# RP5_Left_Board.net
KiCad netlist of a schematic drawn in Altium Designer
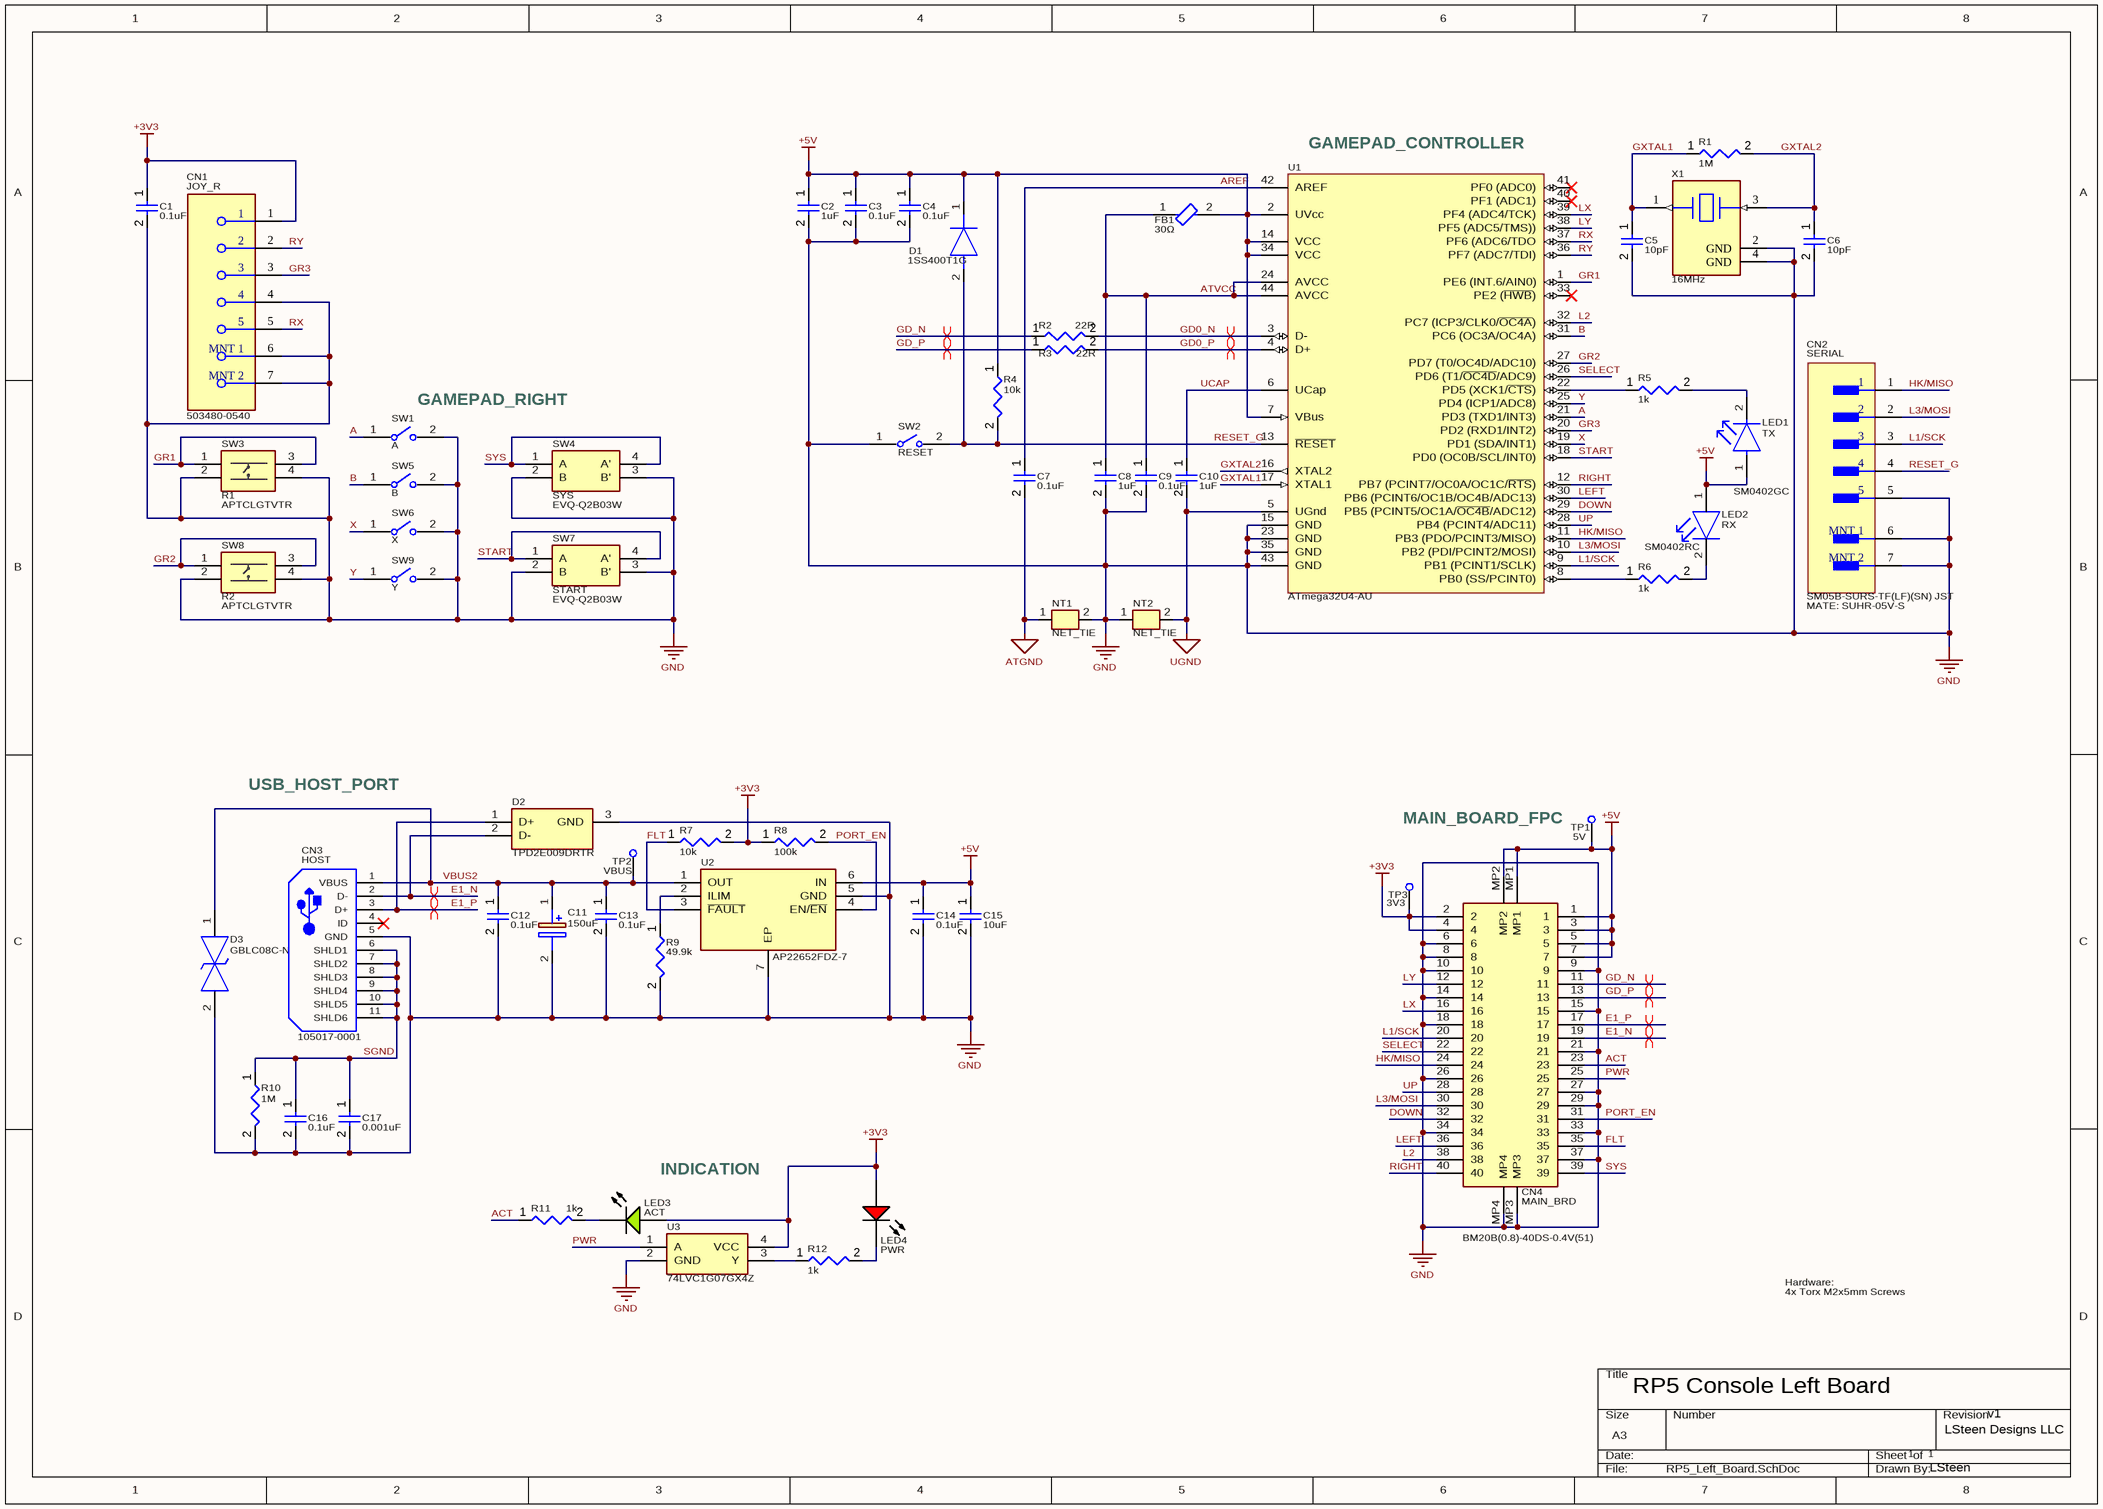
[diagram p0: RP5_Left_Board.SchDoc]

(export (version "E")
  (design (tool "Eeschema 10.0.6"))
  (components
    (comp (ref "C1")
      (value "0.1uF")
      (footprint "CAPC1005X56X25LL10T15")
      (description "Chip Capacitor, 0.1 uF, +/- 5%, 16 V, 0402 (1005 Metric)")
      (fields (field (name "TOLERANCE") "5%"))
      (libsource (lib "Colorado Technical University") (part "CAP-NP-2"))
    )
    (comp (ref "C2")
      (value "1uF")
      (footprint "CAPC0603(1608)100_L")
      (description "Chip Capacitor, 1uF +/-20%, 10V, 0603, Thickness 1 mm")
      (fields (field (name "TOLERANCE") "10%"))
      (libsource (lib "Colorado Technical University") (part "CAP-NP-2"))
    )
    (comp (ref "C3")
      (value "0.1uF")
      (footprint "CAPC1005X56X25LL10T15")
      (description "Chip Capacitor, 0.1 uF, +/- 5%, 16 V, 0402 (1005 Metric)")
      (fields (field (name "TOLERANCE") "5%"))
      (libsource (lib "Colorado Technical University") (part "CAP-NP-2"))
    )
    (comp (ref "C4")
      (value "0.1uF")
      (footprint "CAPC1005X56X25LL10T15")
      (description "Chip Capacitor, 0.1 uF, +/- 5%, 16 V, 0402 (1005 Metric)")
      (fields (field (name "TOLERANCE") "5%"))
      (libsource (lib "Colorado Technical University") (part "CAP-NP-2"))
    )
    (comp (ref "C5")
      (value "10pF")
      (footprint "CAPC1005X56X25LL10T15")
      (description "Chip Capacitor, 10 pF, +/- 5%, 16 V, 0402 (1005 Metric)")
      (fields (field (name "TOLERANCE") "5%"))
      (libsource (lib "Colorado Technical University") (part "CAP-NP-2"))
    )
    (comp (ref "C6")
      (value "10pF")
      (footprint "CAPC1005X56X25LL10T15")
      (description "Chip Capacitor, 10 pF, +/- 5%, 16 V, 0402 (1005 Metric)")
      (fields (field (name "TOLERANCE") "5%"))
      (libsource (lib "Colorado Technical University") (part "CAP-NP-2"))
    )
    (comp (ref "C7")
      (value "0.1uF")
      (footprint "CAPC1005X56X25LL10T15")
      (description "Chip Capacitor, 0.1 uF, +/- 5%, 16 V, 0402 (1005 Metric)")
      (fields (field (name "TOLERANCE") "5%"))
      (libsource (lib "Colorado Technical University") (part "CAP-NP-2"))
    )
    (comp (ref "C8")
      (value "1uF")
      (footprint "CAPC0603(1608)100_L")
      (description "Chip Capacitor, 1uF +/-20%, 10V, 0603, Thickness 1 mm")
      (fields (field (name "TOLERANCE") "10%"))
      (libsource (lib "Colorado Technical University") (part "CAP-NP-2"))
    )
    (comp (ref "C9")
      (value "0.1uF")
      (footprint "CAPC1005X56X25LL10T15")
      (description "Chip Capacitor, 0.1 uF, +/- 5%, 16 V, 0402 (1005 Metric)")
      (fields (field (name "TOLERANCE") "5%"))
      (libsource (lib "Colorado Technical University") (part "CAP-NP-2"))
    )
    (comp (ref "C10")
      (value "1uF")
      (footprint "CAPC0603(1608)100_L")
      (description "Chip Capacitor, 1uF +/-20%, 10V, 0603, Thickness 1 mm")
      (fields (field (name "TOLERANCE") "10%"))
      (libsource (lib "Colorado Technical University") (part "CAP-NP-2"))
    )
    (comp (ref "C11")
      (value "150uF")
      (footprint "SamacSys:CAPPM7344X310N")
      (description "Capacitor Polarised")
      (fields
        (field (name "MANUFACTURER_PART_NUMBER") "TPSD157K016S0125")
        (field (name "MOUSER PART NUMBER") "581-TPSD157K016S0125")
      )
      (libsource (lib "SamacSys") (part "TPSD157K016S0125"))
    )
    (comp (ref "C12")
      (value "0.1uF")
      (footprint "CAPC1005X56X25LL10T15")
      (description "Chip Capacitor, 0.1 uF, +/- 5%, 16 V, 0402 (1005 Metric)")
      (fields (field (name "TOLERANCE") "5%"))
      (libsource (lib "Colorado Technical University") (part "CAP-NP-2"))
    )
    (comp (ref "C13")
      (value "0.1uF")
      (footprint "CAPC1005X56X25LL10T15")
      (description "Chip Capacitor, 0.1 uF, +/- 5%, 16 V, 0402 (1005 Metric)")
      (fields (field (name "TOLERANCE") "5%"))
      (libsource (lib "Colorado Technical University") (part "CAP-NP-2"))
    )
    (comp (ref "C14")
      (value "0.1uF")
      (footprint "CAPC1005X56X25LL10T15")
      (description "Chip Capacitor, 0.1 uF, +/- 5%, 16 V, 0402 (1005 Metric)")
      (fields (field (name "TOLERANCE") "5%"))
      (libsource (lib "Colorado Technical University") (part "CAP-NP-2"))
    )
    (comp (ref "C15")
      (value "10uF")
      (footprint "CAPC0805(2012)145_L")
      (description "Chip Capacitor, 10µF +/-20%, 25V, 0805, Thickness 1.45 mm")
      (fields (field (name "TOLERANCE") "10%"))
      (libsource (lib "Colorado Technical University") (part "CAP-NP-2"))
    )
    (comp (ref "C16")
      (value "0.1uF")
      (footprint "CAPC1005X56X25LL10T15")
      (description "Chip Capacitor, 0.1 uF, +/- 5%, 16 V, 0402 (1005 Metric)")
      (fields (field (name "TOLERANCE") "5%"))
      (libsource (lib "Colorado Technical University") (part "CAP-NP-2"))
    )
    (comp (ref "C17")
      (value "0.001uF")
      (footprint "CAPC1005X56X25LL10T15")
      (description "Chip Capacitor, 0.1 uF, +/- 5%, 16 V, 0402 (1005 Metric)")
      (fields (field (name "TOLERANCE") "5%"))
      (libsource (lib "Colorado Technical University") (part "CAP-NP-2"))
    )
    (comp (ref "CN1")
      (value "JOY_R")
      (footprint "FP-503480-0540-MFG")
      (description "503480-0540 Connector FFC/FPC SKT 5 Position 0.5mm Solder Right Angle Surface Mount T/R")
      (libsource (lib "Altium Content Vault") (part "6b037d2877ced340e1c65ac82253790"))
    )
    (comp (ref "CN2")
      (value "SERIAL")
      (footprint "FP-SM05B-SURS-TF_LF_SN-MFG")
      (description "CONN HEADER SMD R/A 5POS 0.8MM")
      (libsource (lib "Altium Content Vault") (part "SM05B-SURS-TF_LF_SN"))
    )
    (comp (ref "CN3")
      (value "HOST")
      (footprint "105017-0001")
      (description "Micro USB Connector")
      (fields
        (field (name "MANUFACTURER_PART_NUMBER") "105017-0001")
        (field (name "MOUSER PART NUMBER") "538-105017-0001")
      )
      (libsource (lib "SamacSys") (part "105017-0001"))
    )
    (comp (ref "CN4")
      (value "MAIN_BRD")
      (footprint "SamacSys:BM20B0840DS04V51")
      (description "Connector")
      (fields
        (field (name "MANUFACTURER_PART_NUMBER") "BM20B(0.8)-40DS-0.4V(51)")
        (field (name "MOUSER PART NUMBER") "798-BM20B0840DS04V51")
      )
      (libsource (lib "SamacSys") (part "BM20B(0.8)-40DS-0.4V(51)"))
    )
    (comp (ref "D1")
      (value "1SS400T1G")
      (footprint "SamacSys:SODFL1608X70N")
      (description "Diode")
      (fields (field (name "MOUSER PART NUMBER") "863-1SS400T1G"))
      (libsource (lib "SamacSys") (part "1SS400T1G"))
    )
    (comp (ref "D2")
      (value "TPD2E009DRTR")
      (footprint "SamacSys:SOTFL35P100X50-3N")
      (description "Integrated Circuit")
      (fields (field (name "MOUSER PART NUMBER") "595-TPD2E009DRTR"))
      (libsource (lib "SamacSys") (part "TPD2E009DRTR"))
    )
    (comp (ref "D3")
      (value "GBLC08C-N")
      (footprint "SOD-323_L1.8-W1.3-LS2.5-BI")
      (description "ESD DIODE-BI_LCSC#C314256")
      (libsource (lib "Schlib1") (part "GBLC08C-N"))
    )
    (comp (ref "FB1")
      (value "30Ω")
      (footprint "FP-MH2029-MFG")
      (description "FERRITE BEAD 30 OHM 0805 1LN")
      (fields
        (field (name "MANUFACTURER PART NUMBER") "MH2029-300Y")
        (field (name "OCTOPART") "https://octopart.com/mh2029-300y-bourns-756929")
      )
      (libsource (lib "Altium Content Vault") (part "5f30dd21d616792df468990f7003faa"))
    )
    (comp (ref "LED1")
      (value "TX")
      (footprint "FP-SM0402GC-MFG")
      (description "LED GREEN CLEAR 0402 SMD SUPPLIMENT LCSC MHT136CGCT")
      (libsource (lib "Altium Content Vault") (part "ab1c01a81903e929fc6c44469aada92"))
    )
    (comp (ref "LED2")
      (value "RX")
      (footprint "FP-SM0402RC-MFG")
      (description "LED RED CLEAR 0402 SMD SUPPLIMENT LCSC MHT136CRCT")
      (libsource (lib "") (part "ab1c01a81903e929fc6c44469aada92_1"))
    )
    (comp (ref "LED3")
      (value "ACT")
      (footprint "LED_0603")
      (fields (field (name "MPN") "BZ-C0603-K4-E1"))
      (libsource (lib "SamacSys") (part "BZ-C0603-K4-E1"))
    )
    (comp (ref "LED4")
      (value "PWR")
      (footprint "EVRL-0603-2_V")
      (description "Chip LED, Red, 5 V, 25 mA, -40 to 85 degC, 2-Pin SMD (0603), RoHS, Tape and Reel")
      (fields
        (field (name "MANUFACTURER") "Everlight Electronics")
        (field (name "MANUFACTURER PART NUMBER") "19-217/R6C-AL1M2VY/3T")
      )
      (libsource (lib "Altium Content Vault") (part "LED-RED-AK-2"))
    )
    (comp (ref "NT1") (value "NET_TIE") (footprint "NET_TIE1") (libsource (lib "Schlib1") (part "NET_TIE")))
    (comp (ref "NT2") (value "NET_TIE") (footprint "NET_TIE1") (libsource (lib "Schlib1") (part "NET_TIE")))
    (comp (ref "R1")
      (value "1M")
      (footprint "RESC0402(1005)_L")
      (description "Chip Resistor, 1 MOhms, +/-5 %, 63 mW, -55 to 155 degC, 0402")
      (fields (field (name "TOLERANCE") "5%") (field (name "POWER") "63mW"))
      (libsource (lib "Colorado Technical University") (part "RES-2"))
    )
    (comp (ref "R2")
      (value "22R")
      (footprint "RESC0402(1005)_L")
      (description "Chip Resistor, 22 Ohms, +/-5 %, 63 mW, -55 to 155 degC, 0402")
      (fields (field (name "TOLERANCE") "5%") (field (name "POWER") "63mW"))
      (libsource (lib "Colorado Technical University") (part "RES-2"))
    )
    (comp (ref "R3")
      (value "22R")
      (footprint "RESC0402(1005)_L")
      (description "Chip Resistor, 22 Ohms, +/-5 %, 63 mW, -55 to 155 degC, 0402")
      (fields (field (name "TOLERANCE") "5%") (field (name "POWER") "63mW"))
      (libsource (lib "Colorado Technical University") (part "RES-2"))
    )
    (comp (ref "R4")
      (value "10k")
      (footprint "RESC0402(1005)_L")
      (description "Chip Resistor, 10 kOhms, +/-5 %, 63 mW, -55 to 155 degC, 0402")
      (fields (field (name "TOLERANCE") "5%") (field (name "POWER") "63mW"))
      (libsource (lib "Colorado Technical University") (part "RES-2"))
    )
    (comp (ref "R5")
      (value "1k")
      (footprint "RESC0402(1005)_L")
      (description "Chip Resistor, 1 kOhms, +/-5 %, 63 mW, -55 to 155 degC, 0402")
      (fields (field (name "TOLERANCE") "5%") (field (name "POWER") "63mW"))
      (libsource (lib "Colorado Technical University") (part "RES-2"))
    )
    (comp (ref "R6")
      (value "1k")
      (footprint "RESC0402(1005)_L")
      (description "Chip Resistor, 1 kOhms, +/-5 %, 63 mW, -55 to 155 degC, 0402")
      (fields (field (name "TOLERANCE") "5%") (field (name "POWER") "63mW"))
      (libsource (lib "Colorado Technical University") (part "RES-2"))
    )
    (comp (ref "R7")
      (value "10k")
      (footprint "RESC0402(1005)_L")
      (description "Chip Resistor, 10 kOhms, +/-5 %, 63 mW, -55 to 155 degC, 0402")
      (fields (field (name "TOLERANCE") "5%") (field (name "POWER") "63mW"))
      (libsource (lib "Colorado Technical University") (part "RES-2"))
    )
    (comp (ref "R8")
      (value "100k")
      (footprint "RESC0402(1005)_L")
      (description "Chip Resistor, 100 kOhms, +/-5 %, 63 mW, -55 to 155 degC, 0402")
      (fields (field (name "TOLERANCE") "5%") (field (name "POWER") "63mW"))
      (libsource (lib "Colorado Technical University") (part "RES-2"))
    )
    (comp (ref "R9")
      (value "49.9k")
      (footprint "RESC0402(1005)_L")
      (description "Chip Resistor, 49.9 kOhms, +/-5 %, 63 mW, -55 to 155 degC, 0402")
      (fields (field (name "TOLERANCE") "5%") (field (name "POWER") "63mW"))
      (libsource (lib "Colorado Technical University") (part "RES-2"))
    )
    (comp (ref "R10")
      (value "1M")
      (footprint "RESC0402(1005)_L")
      (description "Chip Resistor, 1 MOhms, +/-5 %, 63 mW, -55 to 155 degC, 0402")
      (fields (field (name "TOLERANCE") "5%") (field (name "POWER") "63mW"))
      (libsource (lib "Colorado Technical University") (part "RES-2"))
    )
    (comp (ref "R11")
      (value "1k")
      (footprint "RESC0402(1005)_L")
      (description "Chip Resistor, 1 kOhms, +/-5 %, 63 mW, -55 to 155 degC, 0402")
      (fields (field (name "TOLERANCE") "5%") (field (name "POWER") "63mW"))
      (libsource (lib "Colorado Technical University") (part "RES-2"))
    )
    (comp (ref "R12")
      (value "1k")
      (footprint "RESC0402(1005)_L")
      (description "Chip Resistor, 1 kOhms, +/-5 %, 63 mW, -55 to 155 degC, 0402")
      (fields (field (name "TOLERANCE") "5%") (field (name "POWER") "63mW"))
      (libsource (lib "Colorado Technical University") (part "RES-2"))
    )
    (comp (ref "SW1")
      (value "A")
      (footprint "L4.0-W4.0-CNDV-PAD")
      (description "Conductive Pad Switch")
      (libsource (lib "Schlib1") (part "CNDV_SW"))
    )
    (comp (ref "SW2")
      (value "RESET")
      (footprint "FP-B3U-1000P-MFG")
      (description "LCSC SWITCH TACTILE SPST-NO 0.05A 12V")
      (libsource (lib "Altium Content Vault") (part "ae622034201233ca1abcedc05908f33"))
    )
    (comp (ref "SW3")
      (value "R1")
      (footprint "SamacSys:APTCLGTVTR")
      (description "Switch")
      (fields
        (field (name "MANUFACTURER_PART_NUMBER") "APTCLGTVTR")
        (field (name "MOUSER PART NUMBER") "642-APTCLGTVTR")
      )
      (libsource (lib "SamacSys") (part "APTCLGTVTR"))
    )
    (comp (ref "SW4")
      (value "SYS")
      (footprint "SamacSys:EVQQ2")
      (description "Switch")
      (fields
        (field (name "MANUFACTURER_PART_NUMBER") "EVQ-Q2B03W")
        (field (name "MOUSER PART NUMBER") "667-EVQ-Q2B03W")
      )
      (libsource (lib "SamacSys") (part "EVQ-Q2B03W"))
    )
    (comp (ref "SW5")
      (value "B")
      (footprint "L4.0-W4.0-CNDV-PAD")
      (description "Conductive Pad Switch")
      (libsource (lib "Schlib1") (part "CNDV_SW"))
    )
    (comp (ref "SW6")
      (value "X")
      (footprint "L4.0-W4.0-CNDV-PAD")
      (description "Conductive Pad Switch")
      (libsource (lib "Schlib1") (part "CNDV_SW"))
    )
    (comp (ref "SW7")
      (value "START")
      (footprint "SamacSys:EVQQ2")
      (description "Switch")
      (fields
        (field (name "MANUFACTURER_PART_NUMBER") "EVQ-Q2B03W")
        (field (name "MOUSER PART NUMBER") "667-EVQ-Q2B03W")
      )
      (libsource (lib "SamacSys") (part "EVQ-Q2B03W"))
    )
    (comp (ref "SW8")
      (value "R2")
      (footprint "APTCLGTVTR_No_Holes")
      (description "Switch")
      (fields
        (field (name "MANUFACTURER_PART_NUMBER") "APTCLGTVTR")
        (field (name "MOUSER PART NUMBER") "642-APTCLGTVTR")
      )
      (libsource (lib "SamacSys") (part "APTCLGTVTR_NH"))
    )
    (comp (ref "SW9")
      (value "Y")
      (footprint "L4.0-W4.0-CNDV-PAD")
      (description "Conductive Pad Switch")
      (libsource (lib "Schlib1") (part "CNDV_SW"))
    )
    (comp (ref "TP1")
      (value "5V")
      (footprint "TP")
      (description "TestPoint")
      (libsource (lib "Schlib1") (part "TestPoint"))
    )
    (comp (ref "TP2")
      (value "VBUS")
      (footprint "TP")
      (description "TestPoint")
      (libsource (lib "Schlib1") (part "TestPoint"))
    )
    (comp (ref "TP3")
      (value "3V3")
      (footprint "TP")
      (description "TestPoint")
      (libsource (lib "Schlib1") (part "TestPoint"))
    )
    (comp (ref "U1")
      (value "ATmega32U4-AU")
      (footprint "44ML_M")
      (libsource (lib "Altium Content Vault") (part "MC-8B-ATM16U4-SQ44"))
    )
    (comp (ref "U2")
      (value "AP22652FDZ-7")
      (footprint "SamacSys:SON65P200X200X80-7N-D")
      (description "Integrated Circuit")
      (fields (field (name "MOUSER PART NUMBER") "621-AP22652FDZ-7"))
      (libsource (lib "SamacSys") (part "AP22652FDZ-7"))
    )
    (comp (ref "U3")
      (value "74LVC1G07GX4Z")
      (footprint "SamacSys:74LVC1G07GX4Z")
      (description "Integrated Circuit")
      (fields (field (name "MOUSER PART NUMBER") "771-74LVC1G07GX4Z"))
      (libsource (lib "SamacSys") (part "74LVC1G07GX4Z"))
    )
    (comp (ref "X1")
      (value "16MHz")
      (footprint "FP-ABM8G-MFG")
      (description "Crystal 16MHz ±30ppm (Tol) ±30ppm (Stability) 10pF FUND 80Ω 4-Pin SMD T/R")
      (fields (field (name "TOLERANCE") "30ppm"))
      (libsource (lib "Altium Content Vault") (part "48e526d86b7f2615d98721063c72f49"))
    )
  )
  (nets
    (net (code "1") (name "+3V3") (class "Default")
      (node (ref "C1") (pin "1") (pinfunction "1_1") (pintype "passive"))
      (node (ref "CN1") (pin "1") (pinfunction "1_1") (pintype "passive"))
      (node (ref "CN4") (pin "2") (pinfunction "2_2") (pintype "passive"))
      (node (ref "CN4") (pin "4") (pinfunction "4_4") (pintype "passive"))
      (node (ref "LED3") (pin "1") (pinfunction "A_1") (pintype "passive"))
      (node (ref "LED4") (pin "1") (pinfunction "A_1") (pintype "passive"))
      (node (ref "R7") (pin "2") (pinfunction "2_2") (pintype "passive"))
      (node (ref "R8") (pin "1") (pinfunction "1_1") (pintype "passive"))
      (node (ref "TP3") (pin "1") (pinfunction "1_1") (pintype "passive"))
      (node (ref "U3") (pin "4") (pinfunction "VCC_4") (pintype "passive"))
    )
    (net (code "2") (name "+5V") (class "Default")
      (node (ref "C14") (pin "1") (pinfunction "1_1") (pintype "passive"))
      (node (ref "C15") (pin "1") (pinfunction "1_1") (pintype "passive"))
      (node (ref "C2") (pin "1") (pinfunction "1_1") (pintype "passive"))
      (node (ref "C3") (pin "1") (pinfunction "1_1") (pintype "passive"))
      (node (ref "C4") (pin "1") (pinfunction "1_1") (pintype "passive"))
      (node (ref "CN4") (pin "1") (pinfunction "1_1") (pintype "passive"))
      (node (ref "CN4") (pin "3") (pinfunction "3_3") (pintype "passive"))
      (node (ref "CN4") (pin "5") (pinfunction "5_5") (pintype "passive"))
      (node (ref "CN4") (pin "7") (pinfunction "7_7") (pintype "passive"))
      (node (ref "CN4") (pin "MP1") (pinfunction "MP1_MP1") (pintype "passive"))
      (node (ref "CN4") (pin "MP2") (pinfunction "MP2_MP2") (pintype "passive"))
      (node (ref "D1") (pin "1") (pinfunction "K_1") (pintype "passive"))
      (node (ref "FB1") (pin "2") (pinfunction "2_2") (pintype "passive"))
      (node (ref "LED1") (pin "1") (pinfunction "A_1") (pintype "passive"))
      (node (ref "LED2") (pin "1") (pinfunction "A_1") (pintype "passive"))
      (node (ref "R4") (pin "1") (pinfunction "1_1") (pintype "passive"))
      (node (ref "TP1") (pin "1") (pinfunction "1_1") (pintype "passive"))
      (node (ref "U1") (pin "14") (pinfunction "VCC_14") (pintype "power_in"))
      (node (ref "U1") (pin "2") (pinfunction "UVcc_2") (pintype "power_in"))
      (node (ref "U1") (pin "34") (pinfunction "VCC_34") (pintype "power_in"))
      (node (ref "U1") (pin "7") (pinfunction "VBus_7") (pintype "input"))
      (node (ref "U2") (pin "6") (pinfunction "IN_6") (pintype "passive"))
    )
    (net (code "4") (name "/A") (class "Default")
      (node (ref "SW1") (pin "1") (pinfunction "1_1") (pintype "passive"))
      (node (ref "U1") (pin "21") (pinfunction "PD3_(TXD1/INT3)_21") (pintype "bidirectional"))
    )
    (net (code "5") (name "/ACT") (class "Default")
      (node (ref "CN4") (pin "23") (pinfunction "23_23") (pintype "passive"))
      (node (ref "R11") (pin "1") (pinfunction "1_1") (pintype "passive"))
    )
    (net (code "6") (name "/AREF") (class "Default")
      (node (ref "C7") (pin "1") (pinfunction "1_1") (pintype "passive"))
      (node (ref "U1") (pin "42") (pinfunction "AREF_42") (pintype "passive"))
    )
    (net (code "7") (name "/ATVCC") (class "Default")
      (node (ref "C8") (pin "1") (pinfunction "1_1") (pintype "passive"))
      (node (ref "C9") (pin "1") (pinfunction "1_1") (pintype "passive"))
      (node (ref "FB1") (pin "1") (pinfunction "1_1") (pintype "passive"))
      (node (ref "U1") (pin "24") (pinfunction "AVCC_24") (pintype "power_in"))
      (node (ref "U1") (pin "44") (pinfunction "AVCC_44") (pintype "power_in"))
    )
    (net (code "8") (name "/B") (class "Default")
      (node (ref "SW5") (pin "1") (pinfunction "1_1") (pintype "passive"))
      (node (ref "U1") (pin "31") (pinfunction "PC6_(OC3A/OC4A)_31") (pintype "bidirectional"))
    )
    (net (code "9") (name "/DOWN") (class "Default")
      (node (ref "CN4") (pin "32") (pinfunction "32_32") (pintype "passive"))
      (node (ref "U1") (pin "29") (pinfunction "PB5_(PCINT5/OC1A/~{OC4B}/ADC12)_29") (pintype "bidirectional"))
    )
    (net (code "10") (name "/E1_N") (class "Default")
      (node (ref "CN3") (pin "2") (pinfunction "D-_2") (pintype "passive"))
      (node (ref "CN4") (pin "19") (pinfunction "19_19") (pintype "passive"))
      (node (ref "D2") (pin "2") (pinfunction "D-_2") (pintype "passive"))
    )
    (net (code "11") (name "/E1_P") (class "Default")
      (node (ref "CN3") (pin "3") (pinfunction "D+_3") (pintype "passive"))
      (node (ref "CN4") (pin "17") (pinfunction "17_17") (pintype "passive"))
      (node (ref "D2") (pin "1") (pinfunction "D+_1") (pintype "passive"))
    )
    (net (code "12") (name "/FLT") (class "Default")
      (node (ref "CN4") (pin "35") (pinfunction "35_35") (pintype "passive"))
      (node (ref "R7") (pin "1") (pinfunction "1_1") (pintype "passive"))
      (node (ref "U2") (pin "3") (pinfunction "~{FAULT}_3") (pintype "passive"))
    )
    (net (code "13") (name "/GD0_N") (class "Default")
      (node (ref "R2") (pin "2") (pinfunction "2_2") (pintype "passive"))
      (node (ref "U1") (pin "3") (pinfunction "D-_3") (pintype "bidirectional"))
    )
    (net (code "14") (name "/GD0_P") (class "Default")
      (node (ref "R3") (pin "2") (pinfunction "2_2") (pintype "passive"))
      (node (ref "U1") (pin "4") (pinfunction "D+_4") (pintype "bidirectional"))
    )
    (net (code "15") (name "/GD_N") (class "Default")
      (node (ref "CN4") (pin "11") (pinfunction "11_11") (pintype "passive"))
      (node (ref "R2") (pin "1") (pinfunction "1_1") (pintype "passive"))
    )
    (net (code "16") (name "/GD_P") (class "Default")
      (node (ref "CN4") (pin "13") (pinfunction "13_13") (pintype "passive"))
      (node (ref "R3") (pin "1") (pinfunction "1_1") (pintype "passive"))
    )
    (net (code "17") (name "/GR1") (class "Default")
      (node (ref "SW3") (pin "1") (pinfunction "1_1") (pintype "passive"))
      (node (ref "SW3") (pin "3") (pinfunction "3_3") (pintype "passive"))
      (node (ref "U1") (pin "1") (pinfunction "PE6_(INT.6/AIN0)_1") (pintype "bidirectional"))
    )
    (net (code "18") (name "/GR2") (class "Default")
      (node (ref "SW8") (pin "1") (pinfunction "1_1") (pintype "passive"))
      (node (ref "SW8") (pin "3") (pinfunction "3_3") (pintype "passive"))
      (node (ref "U1") (pin "27") (pinfunction "PD7_(T0/OC4D/ADC10)_27") (pintype "bidirectional"))
    )
    (net (code "19") (name "/GR3") (class "Default")
      (node (ref "CN1") (pin "3") (pinfunction "3_3") (pintype "passive"))
      (node (ref "U1") (pin "20") (pinfunction "PD2_(RXD1/INT2)_20") (pintype "bidirectional"))
    )
    (net (code "20") (name "/GXTAL1") (class "Default")
      (node (ref "C5") (pin "1") (pinfunction "1_1") (pintype "passive"))
      (node (ref "R1") (pin "1") (pinfunction "1_1") (pintype "passive"))
      (node (ref "U1") (pin "17") (pinfunction "XTAL1_17") (pintype "input"))
      (node (ref "X1") (pin "1") (pinfunction "1_1") (pintype "output"))
    )
    (net (code "21") (name "/GXTAL2") (class "Default")
      (node (ref "C6") (pin "1") (pinfunction "1_1") (pintype "passive"))
      (node (ref "R1") (pin "2") (pinfunction "2_2") (pintype "passive"))
      (node (ref "U1") (pin "16") (pinfunction "XTAL2_16") (pintype "output"))
      (node (ref "X1") (pin "3") (pinfunction "3_3") (pintype "input"))
    )
    (net (code "22") (name "/HK{slash}MISO") (class "Default")
      (node (ref "CN2") (pin "1") (pinfunction "1_1") (pintype "passive"))
      (node (ref "CN4") (pin "24") (pinfunction "24_24") (pintype "passive"))
      (node (ref "U1") (pin "11") (pinfunction "PB3_(PDO/PCINT3/MISO)_11") (pintype "bidirectional"))
    )
    (net (code "23") (name "/L1{slash}SCK") (class "Default")
      (node (ref "CN2") (pin "3") (pinfunction "3_3") (pintype "passive"))
      (node (ref "CN4") (pin "20") (pinfunction "20_20") (pintype "passive"))
      (node (ref "U1") (pin "9") (pinfunction "PB1_(PCINT1/SCLK)_9") (pintype "bidirectional"))
    )
    (net (code "24") (name "/L2") (class "Default")
      (node (ref "CN4") (pin "38") (pinfunction "38_38") (pintype "passive"))
      (node (ref "U1") (pin "32") (pinfunction "PC7_(ICP3/CLK0/~{OC4A})_32") (pintype "bidirectional"))
    )
    (net (code "25") (name "/L3{slash}MOSI") (class "Default")
      (node (ref "CN2") (pin "2") (pinfunction "2_2") (pintype "passive"))
      (node (ref "CN4") (pin "30") (pinfunction "30_30") (pintype "passive"))
      (node (ref "U1") (pin "10") (pinfunction "PB2_(PDI/PCINT2/MOSI)_10") (pintype "bidirectional"))
    )
    (net (code "26") (name "/LEFT") (class "Default")
      (node (ref "CN4") (pin "36") (pinfunction "36_36") (pintype "passive"))
      (node (ref "U1") (pin "30") (pinfunction "PB6_(PCINT6/OC1B/OC4B/ADC13)_30") (pintype "bidirectional"))
    )
    (net (code "27") (name "/LX") (class "Default")
      (node (ref "CN4") (pin "16") (pinfunction "16_16") (pintype "passive"))
      (node (ref "U1") (pin "39") (pinfunction "PF4_(ADC4/TCK)_39") (pintype "bidirectional"))
    )
    (net (code "28") (name "/LY") (class "Default")
      (node (ref "CN4") (pin "12") (pinfunction "12_12") (pintype "passive"))
      (node (ref "U1") (pin "38") (pinfunction "PF5_(ADC5/TMS))_38") (pintype "bidirectional"))
    )
    (net (code "29") (name "/PORT_EN") (class "Default")
      (node (ref "CN4") (pin "31") (pinfunction "31_31") (pintype "passive"))
      (node (ref "R8") (pin "2") (pinfunction "2_2") (pintype "passive"))
      (node (ref "U2") (pin "4") (pinfunction "EN/~{EN}_4") (pintype "passive"))
    )
    (net (code "30") (name "/PWR") (class "Default")
      (node (ref "CN4") (pin "25") (pinfunction "25_25") (pintype "passive"))
      (node (ref "U3") (pin "1") (pinfunction "A_1") (pintype "passive"))
    )
    (net (code "31") (name "/RESET_G") (class "Default")
      (node (ref "CN2") (pin "4") (pinfunction "4_4") (pintype "passive"))
      (node (ref "D1") (pin "2") (pinfunction "A_2") (pintype "passive"))
      (node (ref "R4") (pin "2") (pinfunction "2_2") (pintype "passive"))
      (node (ref "SW2") (pin "2") (pinfunction "2_2") (pintype "passive"))
      (node (ref "U1") (pin "13") (pinfunction "~{RESET}_13") (pintype "passive"))
    )
    (net (code "32") (name "/RIGHT") (class "Default")
      (node (ref "CN4") (pin "40") (pinfunction "40_40") (pintype "passive"))
      (node (ref "U1") (pin "12") (pinfunction "PB7_(PCINT7/OC0A/OC1C/~{RTS})_12") (pintype "bidirectional"))
    )
    (net (code "33") (name "/RX") (class "Default")
      (node (ref "CN1") (pin "5") (pinfunction "5_5") (pintype "passive"))
      (node (ref "U1") (pin "37") (pinfunction "PF6_(ADC6/TDO_37") (pintype "bidirectional"))
    )
    (net (code "34") (name "/RY") (class "Default")
      (node (ref "CN1") (pin "2") (pinfunction "2_2") (pintype "passive"))
      (node (ref "U1") (pin "36") (pinfunction "PF7_(ADC7/TDI)_36") (pintype "bidirectional"))
    )
    (net (code "35") (name "/SELECT") (class "Default")
      (node (ref "CN4") (pin "22") (pinfunction "22_22") (pintype "passive"))
      (node (ref "U1") (pin "26") (pinfunction "PD6_(T1/~{OC4D}/ADC9)_26") (pintype "bidirectional"))
    )
    (net (code "36") (name "/SGND") (class "Default")
      (node (ref "C16") (pin "1") (pinfunction "1_1") (pintype "passive"))
      (node (ref "C17") (pin "1") (pinfunction "1_1") (pintype "passive"))
      (node (ref "CN3") (pin "10") (pinfunction "SHLD5_10") (pintype "passive"))
      (node (ref "CN3") (pin "11") (pinfunction "SHLD6_11") (pintype "passive"))
      (node (ref "CN3") (pin "6") (pinfunction "SHLD1_6") (pintype "passive"))
      (node (ref "CN3") (pin "7") (pinfunction "SHLD2_7") (pintype "passive"))
      (node (ref "CN3") (pin "8") (pinfunction "SHLD3_8") (pintype "passive"))
      (node (ref "CN3") (pin "9") (pinfunction "SHLD4_9") (pintype "passive"))
      (node (ref "R10") (pin "1") (pinfunction "1_1") (pintype "passive"))
    )
    (net (code "37") (name "/START") (class "Default")
      (node (ref "SW7") (pin "1") (pinfunction "A_1") (pintype "passive"))
      (node (ref "SW7") (pin "4") (pinfunction "A'_4") (pintype "passive"))
      (node (ref "U1") (pin "18") (pinfunction "PD0_(OC0B/SCL/INT0)_18") (pintype "bidirectional"))
    )
    (net (code "38") (name "/SYS") (class "Default")
      (node (ref "CN4") (pin "39") (pinfunction "39_39") (pintype "passive"))
      (node (ref "SW4") (pin "1") (pinfunction "A_1") (pintype "passive"))
      (node (ref "SW4") (pin "4") (pinfunction "A'_4") (pintype "passive"))
    )
    (net (code "39") (name "/UCAP") (class "Default")
      (node (ref "C10") (pin "1") (pinfunction "1_1") (pintype "passive"))
      (node (ref "U1") (pin "6") (pinfunction "UCap_6") (pintype "passive"))
    )
    (net (code "40") (name "/UP") (class "Default")
      (node (ref "CN4") (pin "28") (pinfunction "28_28") (pintype "passive"))
      (node (ref "U1") (pin "28") (pinfunction "PB4_(PCINT4/ADC11)_28") (pintype "bidirectional"))
    )
    (net (code "41") (name "/VBUS2") (class "Default")
      (node (ref "C11") (pin "1") (pinfunction "+_1") (pintype "passive"))
      (node (ref "C12") (pin "1") (pinfunction "1_1") (pintype "passive"))
      (node (ref "C13") (pin "1") (pinfunction "1_1") (pintype "passive"))
      (node (ref "CN3") (pin "1") (pinfunction "VBUS_1") (pintype "passive"))
      (node (ref "D3") (pin "1") (pinfunction "1_1") (pintype "passive"))
      (node (ref "TP2") (pin "1") (pinfunction "1_1") (pintype "passive"))
      (node (ref "U2") (pin "1") (pinfunction "OUT_1") (pintype "passive"))
    )
    (net (code "42") (name "/X") (class "Default")
      (node (ref "SW6") (pin "1") (pinfunction "1_1") (pintype "passive"))
      (node (ref "U1") (pin "19") (pinfunction "PD1_(SDA/INT1)_19") (pintype "bidirectional"))
    )
    (net (code "43") (name "/Y") (class "Default")
      (node (ref "SW9") (pin "1") (pinfunction "1_1") (pintype "passive"))
      (node (ref "U1") (pin "25") (pinfunction "PD4_(ICP1/ADC8)_25") (pintype "bidirectional"))
    )
    (net (code "44") (name "ATGND") (class "Default")
      (node (ref "C7") (pin "2") (pinfunction "2_2") (pintype "passive"))
      (node (ref "NT1") (pin "1") (pintype "passive"))
    )
    (net (code "45") (name "GND") (class "Default")
      (node (ref "C1") (pin "2") (pinfunction "2_2") (pintype "passive"))
      (node (ref "C11") (pin "2") (pinfunction "-_2") (pintype "passive"))
      (node (ref "C12") (pin "2") (pinfunction "2_2") (pintype "passive"))
      (node (ref "C13") (pin "2") (pinfunction "2_2") (pintype "passive"))
      (node (ref "C14") (pin "2") (pinfunction "2_2") (pintype "passive"))
      (node (ref "C15") (pin "2") (pinfunction "2_2") (pintype "passive"))
      (node (ref "C16") (pin "2") (pinfunction "2_2") (pintype "passive"))
      (node (ref "C17") (pin "2") (pinfunction "2_2") (pintype "passive"))
      (node (ref "C2") (pin "2") (pinfunction "2_2") (pintype "passive"))
      (node (ref "C3") (pin "2") (pinfunction "2_2") (pintype "passive"))
      (node (ref "C4") (pin "2") (pinfunction "2_2") (pintype "passive"))
      (node (ref "C5") (pin "2") (pinfunction "2_2") (pintype "passive"))
      (node (ref "C6") (pin "2") (pinfunction "2_2") (pintype "passive"))
      (node (ref "C8") (pin "2") (pinfunction "2_2") (pintype "passive"))
      (node (ref "C9") (pin "2") (pinfunction "2_2") (pintype "passive"))
      (node (ref "CN1") (pin "4") (pinfunction "4_4") (pintype "passive"))
      (node (ref "CN1") (pin "6") (pinfunction "MNT_1_6") (pintype "passive"))
      (node (ref "CN1") (pin "7") (pinfunction "MNT_2_7") (pintype "passive"))
      (node (ref "CN2") (pin "5") (pinfunction "5_5") (pintype "passive"))
      (node (ref "CN2") (pin "6") (pinfunction "MNT_1_6") (pintype "passive"))
      (node (ref "CN2") (pin "7") (pinfunction "MNT_2_7") (pintype "passive"))
      (node (ref "CN3") (pin "5") (pinfunction "GND_5") (pintype "passive"))
      (node (ref "CN4") (pin "10") (pinfunction "10_10") (pintype "passive"))
      (node (ref "CN4") (pin "14") (pinfunction "14_14") (pintype "passive"))
      (node (ref "CN4") (pin "15") (pinfunction "15_15") (pintype "passive"))
      (node (ref "CN4") (pin "18") (pinfunction "18_18") (pintype "passive"))
      (node (ref "CN4") (pin "21") (pinfunction "21_21") (pintype "passive"))
      (node (ref "CN4") (pin "26") (pinfunction "26_26") (pintype "passive"))
      (node (ref "CN4") (pin "27") (pinfunction "27_27") (pintype "passive"))
      (node (ref "CN4") (pin "29") (pinfunction "29_29") (pintype "passive"))
      (node (ref "CN4") (pin "33") (pinfunction "33_33") (pintype "passive"))
      (node (ref "CN4") (pin "34") (pinfunction "34_34") (pintype "passive"))
      (node (ref "CN4") (pin "37") (pinfunction "37_37") (pintype "passive"))
      (node (ref "CN4") (pin "6") (pinfunction "6_6") (pintype "passive"))
      (node (ref "CN4") (pin "8") (pinfunction "8_8") (pintype "passive"))
      (node (ref "CN4") (pin "9") (pinfunction "9_9") (pintype "passive"))
      (node (ref "CN4") (pin "MP3") (pinfunction "MP3_MP3") (pintype "passive"))
      (node (ref "CN4") (pin "MP4") (pinfunction "MP4_MP4") (pintype "passive"))
      (node (ref "D2") (pin "3") (pinfunction "GND_3") (pintype "passive"))
      (node (ref "D3") (pin "2") (pinfunction "2_2") (pintype "passive"))
      (node (ref "NT1") (pin "2") (pintype "passive"))
      (node (ref "NT2") (pin "1") (pintype "passive"))
      (node (ref "R10") (pin "2") (pinfunction "2_2") (pintype "passive"))
      (node (ref "R9") (pin "2") (pinfunction "2_2") (pintype "passive"))
      (node (ref "SW1") (pin "2") (pinfunction "2_2") (pintype "passive"))
      (node (ref "SW2") (pin "1") (pinfunction "1_1") (pintype "passive"))
      (node (ref "SW3") (pin "2") (pinfunction "2_2") (pintype "passive"))
      (node (ref "SW3") (pin "4") (pinfunction "4_4") (pintype "passive"))
      (node (ref "SW4") (pin "2") (pinfunction "B_2") (pintype "passive"))
      (node (ref "SW4") (pin "3") (pinfunction "B'_3") (pintype "passive"))
      (node (ref "SW5") (pin "2") (pinfunction "2_2") (pintype "passive"))
      (node (ref "SW6") (pin "2") (pinfunction "2_2") (pintype "passive"))
      (node (ref "SW7") (pin "2") (pinfunction "B_2") (pintype "passive"))
      (node (ref "SW7") (pin "3") (pinfunction "B'_3") (pintype "passive"))
      (node (ref "SW8") (pin "2") (pinfunction "2_2") (pintype "passive"))
      (node (ref "SW8") (pin "4") (pinfunction "4_4") (pintype "passive"))
      (node (ref "SW9") (pin "2") (pinfunction "2_2") (pintype "passive"))
      (node (ref "U1") (pin "15") (pinfunction "GND_15") (pintype "power_in"))
      (node (ref "U1") (pin "23") (pinfunction "GND_23") (pintype "power_in"))
      (node (ref "U1") (pin "35") (pinfunction "GND_35") (pintype "power_in"))
      (node (ref "U1") (pin "43") (pinfunction "GND_43") (pintype "power_in"))
      (node (ref "U2") (pin "5") (pinfunction "GND_5") (pintype "passive"))
      (node (ref "U2") (pin "7") (pinfunction "EP_7") (pintype "passive"))
      (node (ref "U3") (pin "2") (pinfunction "GND_2") (pintype "passive"))
      (node (ref "X1") (pin "2") (pinfunction "GND_2") (pintype "power_in"))
      (node (ref "X1") (pin "4") (pinfunction "GND_4") (pintype "power_in"))
    )
    (net (code "46") (name "Net-(LED1-C)") (class "Default")
      (node (ref "LED1") (pin "2") (pinfunction "C_2") (pintype "passive"))
      (node (ref "R5") (pin "2") (pinfunction "2_2") (pintype "passive"))
    )
    (net (code "47") (name "Net-(LED2-C)") (class "Default")
      (node (ref "LED2") (pin "2") (pinfunction "C_2") (pintype "passive"))
      (node (ref "R6") (pin "2") (pinfunction "2_2") (pintype "passive"))
    )
    (net (code "48") (name "Net-(LED3-K)") (class "Default")
      (node (ref "LED3") (pin "2") (pinfunction "K_2") (pintype "passive"))
      (node (ref "R11") (pin "2") (pinfunction "2_2") (pintype "passive"))
    )
    (net (code "49") (name "Net-(LED4-K)") (class "Default")
      (node (ref "LED4") (pin "2") (pinfunction "K_2") (pintype "passive"))
      (node (ref "R12") (pin "2") (pinfunction "2_2") (pintype "passive"))
    )
    (net (code "50") (name "Net-(U1-PB0_(SS{slash}PCINT0))") (class "Default")
      (node (ref "R6") (pin "1") (pinfunction "1_1") (pintype "passive"))
      (node (ref "U1") (pin "8") (pinfunction "PB0_(SS/PCINT0)_8") (pintype "bidirectional"))
    )
    (net (code "51") (name "Net-(U1-PD5_(XCK1{slash}~{CTS}))") (class "Default")
      (node (ref "R5") (pin "1") (pinfunction "1_1") (pintype "passive"))
      (node (ref "U1") (pin "22") (pinfunction "PD5_(XCK1/~{CTS})_22") (pintype "bidirectional"))
    )
    (net (code "52") (name "Net-(U2-ILIM)") (class "Default")
      (node (ref "R9") (pin "1") (pinfunction "1_1") (pintype "passive"))
      (node (ref "U2") (pin "2") (pinfunction "ILIM_2") (pintype "passive"))
    )
    (net (code "53") (name "Net-(U3-Y)") (class "Default")
      (node (ref "R12") (pin "1") (pinfunction "1_1") (pintype "passive"))
      (node (ref "U3") (pin "3") (pinfunction "Y_3") (pintype "passive"))
    )
    (net (code "54") (name "UGND") (class "Default")
      (node (ref "C10") (pin "2") (pinfunction "2_2") (pintype "passive"))
      (node (ref "NT2") (pin "2") (pintype "passive"))
      (node (ref "U1") (pin "5") (pinfunction "UGnd_5") (pintype "power_in"))
    )
    (net (code "55") (name "unconnected-(CN3-ID-Pad4)") (class "Default")
      (node (ref "CN3") (pin "4") (pinfunction "ID_4") (pintype "passive+no_connect"))
    )
    (net (code "56") (name "unconnected-(U1-PE2_(~{HWB})-Pad33)") (class "Default")
      (node (ref "U1") (pin "33") (pinfunction "PE2_(~{HWB})_33") (pintype "bidirectional+no_connect"))
    )
    (net (code "57") (name "unconnected-(U1-PF0_(ADC0)-Pad41)") (class "Default")
      (node (ref "U1") (pin "41") (pinfunction "PF0_(ADC0)_41") (pintype "bidirectional+no_connect"))
    )
    (net (code "58") (name "unconnected-(U1-PF1_(ADC1)-Pad40)") (class "Default")
      (node (ref "U1") (pin "40") (pinfunction "PF1_(ADC1)_40") (pintype "bidirectional+no_connect"))
    )
  )
)
